# ESP32S3.net
KiCad netlist of a schematic drawn in Altium Designer
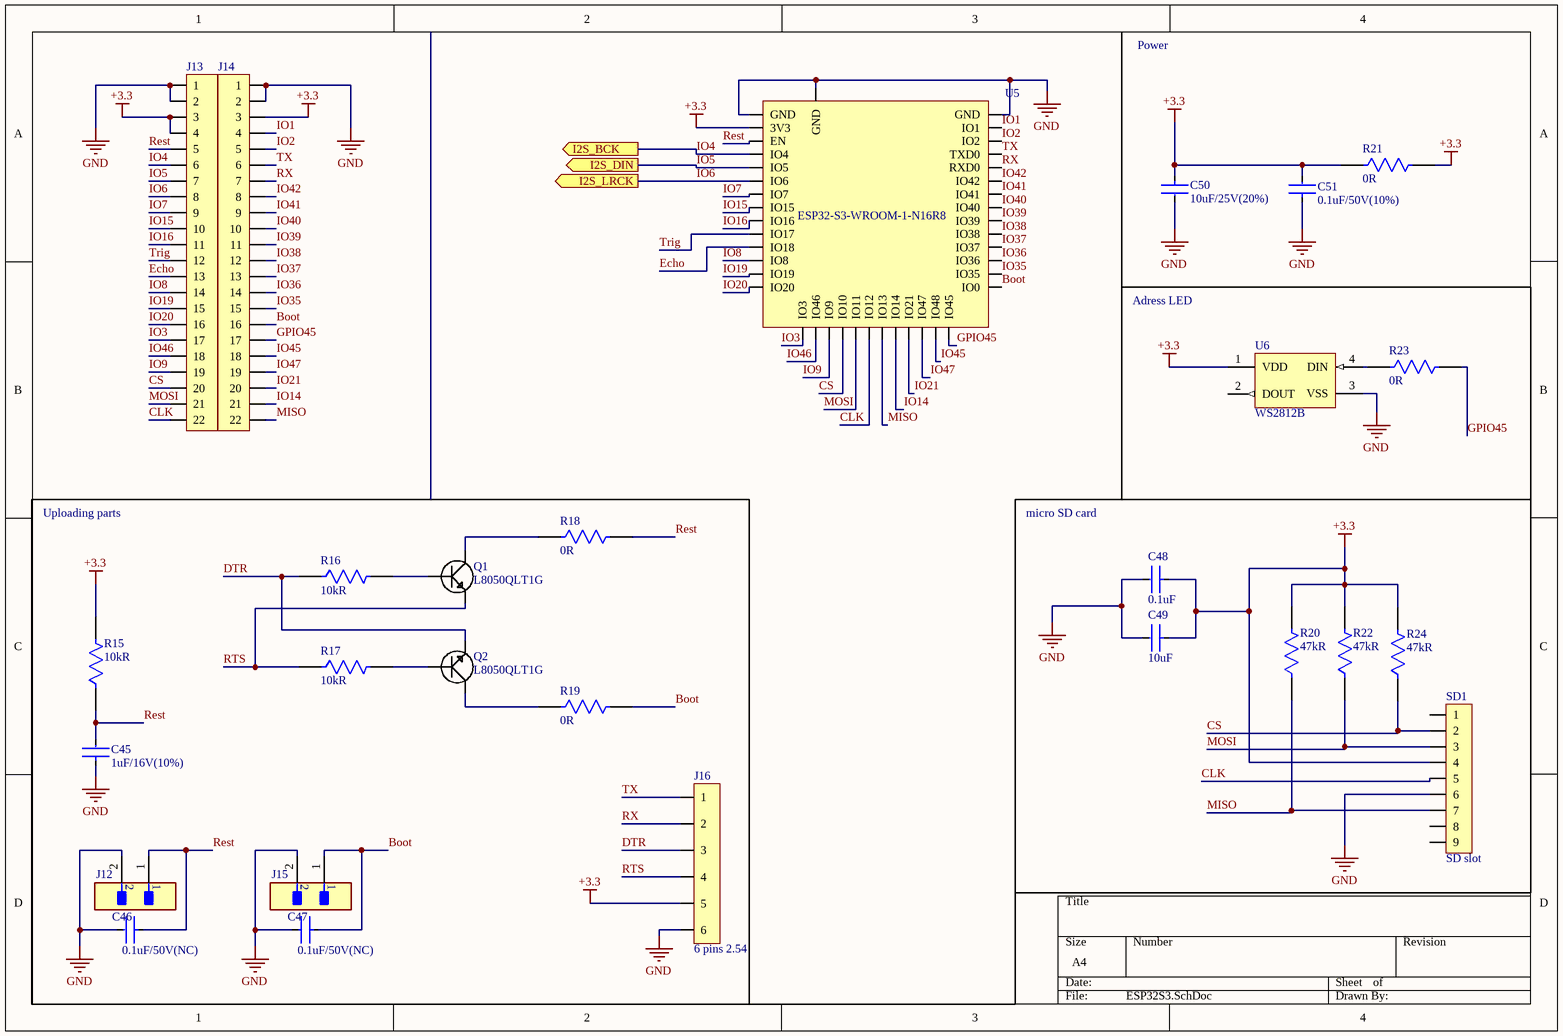
[diagram p0: ESP32S3.SchDoc]

(export (version "E")
  (design (tool "Eeschema 10.0.6"))
  (components
    (comp (ref "C45")
      (value "1uF/16V(10%)")
      (footprint "FP-CL21-IPC_C")
      (description "CL21 Series 0805 47nF 50V ±5% Tolerance X7R Multilayer Ceramic Chip Capacitor")
      (fields (field (name "TOLERANCE") "5%"))
      (libsource (lib "Altium Content Vault") (part "b4654b650e69147ec39a6b967a45e02"))
    )
    (comp (ref "C46")
      (value "0.1uF/50V(NC)")
      (footprint "FP-CL21-IPC_C")
      (description "CL21 Series 0805 47nF 50V ±5% Tolerance X7R Multilayer Ceramic Chip Capacitor")
      (fields (field (name "TOLERANCE") "5%"))
      (libsource (lib "Altium Content Vault") (part "b4654b650e69147ec39a6b967a45e02"))
    )
    (comp (ref "C47")
      (value "0.1uF/50V(NC)")
      (footprint "FP-CL21-IPC_C")
      (description "CL21 Series 0805 47nF 50V ±5% Tolerance X7R Multilayer Ceramic Chip Capacitor")
      (fields (field (name "TOLERANCE") "5%"))
      (libsource (lib "Altium Content Vault") (part "b4654b650e69147ec39a6b967a45e02"))
    )
    (comp (ref "C48")
      (value "0.1uF")
      (footprint "FP-CL21-IPC_C")
      (description "CL21 Series 0805 47nF 50V ±5% Tolerance X7R Multilayer Ceramic Chip Capacitor")
      (fields (field (name "TOLERANCE") "5%"))
      (libsource (lib "Altium Content Vault") (part "b4654b650e69147ec39a6b967a45e02"))
    )
    (comp (ref "C49")
      (value "10uF")
      (footprint "FP-CL21-IPC_C")
      (description "CL21 Series 0805 47nF 50V ±5% Tolerance X7R Multilayer Ceramic Chip Capacitor")
      (fields (field (name "TOLERANCE") "5%"))
      (libsource (lib "Altium Content Vault") (part "b4654b650e69147ec39a6b967a45e02"))
    )
    (comp (ref "C50")
      (value "10uF/25V(20%)")
      (footprint "FP-CL21-IPC_C")
      (description "CL21 Series 0805 47nF 50V ±5% Tolerance X7R Multilayer Ceramic Chip Capacitor")
      (fields (field (name "TOLERANCE") "5%"))
      (libsource (lib "Altium Content Vault") (part "b4654b650e69147ec39a6b967a45e02"))
    )
    (comp (ref "C51")
      (value "0.1uF/50V(10%)")
      (footprint "FP-CL21-IPC_C")
      (description "CL21 Series 0805 47nF 50V ±5% Tolerance X7R Multilayer Ceramic Chip Capacitor")
      (fields (field (name "TOLERANCE") "5%"))
      (libsource (lib "Altium Content Vault") (part "b4654b650e69147ec39a6b967a45e02"))
    )
    (comp (ref "J12")
      (value "M22-2510205")
      (footprint "FP-M22-2510205-MFG")
      (description "CONN HEADER VERT 2POS 2MM")
      (fields
        (field (name "MANUFACTURER") "Harwin")
        (field (name "OCTOPART") "https://octopart.com/m22-2510205-harwin-2538221")
      )
      (libsource (lib "Altium Content Vault") (part "3bc925449376181038e59eaffc5286c"))
    )
    (comp (ref "J13")
      (value "22 pins")
      (footprint "22 pins")
      (libsource (lib "Schemati_design") (part "22 pins"))
    )
    (comp (ref "J14") (value "22 pins") (footprint "22 pins") (libsource (lib "") (part "22 pins_1")))
    (comp (ref "J15")
      (value "M22-2510205")
      (footprint "FP-M22-2510205-MFG")
      (description "CONN HEADER VERT 2POS 2MM")
      (fields
        (field (name "MANUFACTURER") "Harwin")
        (field (name "OCTOPART") "https://octopart.com/m22-2510205-harwin-2538221")
      )
      (libsource (lib "Altium Content Vault") (part "3bc925449376181038e59eaffc5286c"))
    )
    (comp (ref "J16")
      (value "6 pins 2.54")
      (footprint "6 pins 2.54mm")
      (libsource (lib "Schemati_design") (part "6 pins 2.54"))
    )
    (comp (ref "Q1")
      (value "L8050QLT1G")
      (footprint "SOT95P245X110-3N")
      (libsource (lib "Schemati_design") (part "L8050QLT1G"))
    )
    (comp (ref "Q2")
      (value "L8050QLT1G")
      (footprint "SOT95P245X110-3N")
      (libsource (lib "Schemati_design") (part "L8050QLT1G"))
    )
    (comp (ref "R15")
      (value "10kR")
      (footprint "FP-RP732A-IPC_C")
      (fields (field (name "TOLERANCE") "0.1%"))
      (libsource (lib "Altium Content Vault") (part "1029c3af85768c4190bb7ad29bc67b5"))
    )
    (comp (ref "R16")
      (value "10kR")
      (footprint "FP-RP732A-IPC_C")
      (fields (field (name "TOLERANCE") "0.1%"))
      (libsource (lib "Altium Content Vault") (part "1029c3af85768c4190bb7ad29bc67b5"))
    )
    (comp (ref "R17")
      (value "10kR")
      (footprint "FP-RP732A-IPC_C")
      (fields (field (name "TOLERANCE") "0.1%"))
      (libsource (lib "Altium Content Vault") (part "1029c3af85768c4190bb7ad29bc67b5"))
    )
    (comp (ref "R18")
      (value "0R")
      (footprint "FP-RP732A-IPC_C")
      (fields (field (name "TOLERANCE") "0.1%"))
      (libsource (lib "Altium Content Vault") (part "1029c3af85768c4190bb7ad29bc67b5"))
    )
    (comp (ref "R19")
      (value "0R")
      (footprint "FP-RP732A-IPC_C")
      (fields (field (name "TOLERANCE") "0.1%"))
      (libsource (lib "Altium Content Vault") (part "1029c3af85768c4190bb7ad29bc67b5"))
    )
    (comp (ref "R20")
      (value "47kR")
      (footprint "FP-RP732A-IPC_C")
      (fields (field (name "TOLERANCE") "0.1%"))
      (libsource (lib "Altium Content Vault") (part "1029c3af85768c4190bb7ad29bc67b5"))
    )
    (comp (ref "R21")
      (value "0R")
      (footprint "FP-RP732A-IPC_C")
      (fields (field (name "TOLERANCE") "0.1%"))
      (libsource (lib "Altium Content Vault") (part "1029c3af85768c4190bb7ad29bc67b5"))
    )
    (comp (ref "R22")
      (value "47kR")
      (footprint "FP-RP732A-IPC_C")
      (fields (field (name "TOLERANCE") "0.1%"))
      (libsource (lib "Altium Content Vault") (part "1029c3af85768c4190bb7ad29bc67b5"))
    )
    (comp (ref "R23")
      (value "0R")
      (footprint "FP-RP732A-IPC_C")
      (fields (field (name "TOLERANCE") "0.1%"))
      (libsource (lib "Altium Content Vault") (part "1029c3af85768c4190bb7ad29bc67b5"))
    )
    (comp (ref "R24")
      (value "47kR")
      (footprint "FP-RP732A-IPC_C")
      (fields (field (name "TOLERANCE") "0.1%"))
      (libsource (lib "Altium Content Vault") (part "1029c3af85768c4190bb7ad29bc67b5"))
    )
    (comp (ref "SD1")
      (value "SD slot")
      (footprint "Micro SD slot")
      (libsource (lib "Schemati_design") (part "SD slot"))
    )
    (comp (ref "U5")
      (value "ESP32-S3-WROOM-1-N16R8")
      (footprint "ESP32_S3_Wroom1")
      (description "SMD mod, ESP32-S3R8 with 3.3V, 8MB Octal PSRAM die insid, 6MBQuad SPI flash, pcb ant")
      (fields (field (name "MANUFACTURER") "Espressif Systems"))
      (libsource (lib "Schemati_design") (part "ESP32-S3-WROOM-1-N16R8"))
    )
    (comp (ref "U6")
      (value "WS2812B")
      (footprint "ADA-RGB-1655_V")
      (fields (field (name "MANUFACTURER") "Adafruit-Industries-LLC"))
      (libsource (lib "Altium Content Vault") (part "ADA-RGB-1655-4"))
    )
  )
  (nets
    (net (code "1") (name "+3.3") (class "Default")
      (node (ref "C48") (pin "1") (pinfunction "1_1") (pintype "passive"))
      (node (ref "C49") (pin "1") (pinfunction "1_1") (pintype "passive"))
      (node (ref "C50") (pin "1") (pinfunction "1_1") (pintype "passive"))
      (node (ref "C51") (pin "2") (pinfunction "2_2") (pintype "passive"))
      (node (ref "J13") (pin "3") (pinfunction "3_3") (pintype "passive"))
      (node (ref "J13") (pin "4") (pinfunction "4_4") (pintype "passive"))
      (node (ref "J14") (pin "3") (pinfunction "3_3") (pintype "passive"))
      (node (ref "J16") (pin "5") (pinfunction "5_5") (pintype "passive"))
      (node (ref "R15") (pin "2") (pinfunction "2_2") (pintype "passive"))
      (node (ref "R20") (pin "2") (pinfunction "2_2") (pintype "passive"))
      (node (ref "R21") (pin "1") (pinfunction "1_1") (pintype "passive"))
      (node (ref "R21") (pin "2") (pinfunction "2_2") (pintype "passive"))
      (node (ref "R22") (pin "2") (pinfunction "2_2") (pintype "passive"))
      (node (ref "R24") (pin "2") (pinfunction "2_2") (pintype "passive"))
      (node (ref "SD1") (pin "4") (pinfunction "4_4") (pintype "passive"))
      (node (ref "U5") (pin "2") (pinfunction "3V3_2") (pintype "passive"))
      (node (ref "U6") (pin "1") (pinfunction "VDD_1") (pintype "power_in"))
    )
    (net (code "2") (name "/Boot") (class "Default")
      (node (ref "C47") (pin "1") (pinfunction "1_1") (pintype "passive"))
      (node (ref "J14") (pin "16") (pinfunction "16_16") (pintype "passive"))
      (node (ref "J15") (pin "1") (pinfunction "1_1") (pintype "passive"))
      (node (ref "R19") (pin "2") (pinfunction "2_2") (pintype "passive"))
      (node (ref "U5") (pin "27") (pinfunction "IO0_27") (pintype "passive"))
    )
    (net (code "3") (name "/CLK") (class "Default")
      (node (ref "J13") (pin "22") (pinfunction "22_22") (pintype "passive"))
      (node (ref "SD1") (pin "5") (pinfunction "5_5") (pintype "passive"))
      (node (ref "U5") (pin "20") (pinfunction "IO12_20") (pintype "passive"))
    )
    (net (code "4") (name "/CS") (class "Default")
      (node (ref "J13") (pin "20") (pinfunction "20_20") (pintype "passive"))
      (node (ref "R24") (pin "1") (pinfunction "1_1") (pintype "passive"))
      (node (ref "SD1") (pin "2") (pinfunction "2_2") (pintype "passive"))
      (node (ref "U5") (pin "18") (pinfunction "IO10_18") (pintype "passive"))
    )
    (net (code "5") (name "/DTR") (class "Default")
      (node (ref "J16") (pin "3") (pinfunction "3_3") (pintype "passive"))
      (node (ref "Q2") (pin "2") (pinfunction "Emitter_2") (pintype "passive"))
      (node (ref "R16") (pin "1") (pinfunction "1_1") (pintype "passive"))
    )
    (net (code "6") (name "/Echo") (class "Default")
      (node (ref "J13") (pin "13") (pinfunction "13_13") (pintype "passive"))
      (node (ref "U5") (pin "11") (pinfunction "IO18_11") (pintype "passive"))
    )
    (net (code "7") (name "/GPIO45") (class "Default")
      (node (ref "J14") (pin "17") (pinfunction "17_17") (pintype "passive"))
      (node (ref "R23") (pin "2") (pinfunction "2_2") (pintype "passive"))
      (node (ref "U5") (pin "26") (pinfunction "IO45_26") (pintype "passive"))
    )
    (net (code "8") (name "/IO1") (class "Default")
      (node (ref "J14") (pin "4") (pinfunction "4_4") (pintype "passive"))
      (node (ref "U5") (pin "39") (pinfunction "IO1_39") (pintype "passive"))
    )
    (net (code "9") (name "/IO2") (class "Default")
      (node (ref "J14") (pin "5") (pinfunction "5_5") (pintype "passive"))
      (node (ref "U5") (pin "38") (pinfunction "IO2_38") (pintype "passive"))
    )
    (net (code "10") (name "/IO3") (class "Default")
      (node (ref "J13") (pin "17") (pinfunction "17_17") (pintype "passive"))
      (node (ref "U5") (pin "15") (pinfunction "IO3_15") (pintype "passive"))
    )
    (net (code "11") (name "/IO4") (class "Default")
      (node (ref "J13") (pin "6") (pinfunction "6_6") (pintype "passive"))
      (node (ref "U5") (pin "4") (pinfunction "IO4_4") (pintype "passive"))
    )
    (net (code "12") (name "/IO5") (class "Default")
      (node (ref "J13") (pin "7") (pinfunction "7_7") (pintype "passive"))
      (node (ref "U5") (pin "5") (pinfunction "IO5_5") (pintype "passive"))
    )
    (net (code "13") (name "/IO6") (class "Default")
      (node (ref "J13") (pin "8") (pinfunction "8_8") (pintype "passive"))
      (node (ref "U5") (pin "6") (pinfunction "IO6_6") (pintype "passive"))
    )
    (net (code "14") (name "/IO7") (class "Default")
      (node (ref "J13") (pin "9") (pinfunction "9_9") (pintype "passive"))
      (node (ref "U5") (pin "7") (pinfunction "IO7_7") (pintype "passive"))
    )
    (net (code "15") (name "/IO8") (class "Default")
      (node (ref "J13") (pin "14") (pinfunction "14_14") (pintype "passive"))
      (node (ref "U5") (pin "12") (pinfunction "IO8_12") (pintype "passive"))
    )
    (net (code "16") (name "/IO9") (class "Default")
      (node (ref "J13") (pin "19") (pinfunction "19_19") (pintype "passive"))
      (node (ref "U5") (pin "17") (pinfunction "IO9_17") (pintype "passive"))
    )
    (net (code "17") (name "/IO14") (class "Default")
      (node (ref "J14") (pin "21") (pinfunction "21_21") (pintype "passive"))
      (node (ref "U5") (pin "22") (pinfunction "IO14_22") (pintype "passive"))
    )
    (net (code "18") (name "/IO15") (class "Default")
      (node (ref "J13") (pin "10") (pinfunction "10_10") (pintype "passive"))
      (node (ref "U5") (pin "8") (pinfunction "IO15_8") (pintype "passive"))
    )
    (net (code "19") (name "/IO16") (class "Default")
      (node (ref "J13") (pin "11") (pinfunction "11_11") (pintype "passive"))
      (node (ref "U5") (pin "9") (pinfunction "IO16_9") (pintype "passive"))
    )
    (net (code "20") (name "/IO19") (class "Default")
      (node (ref "J13") (pin "15") (pinfunction "15_15") (pintype "passive"))
      (node (ref "U5") (pin "13") (pinfunction "IO19_13") (pintype "passive"))
    )
    (net (code "21") (name "/IO20") (class "Default")
      (node (ref "J13") (pin "16") (pinfunction "16_16") (pintype "passive"))
      (node (ref "U5") (pin "14") (pinfunction "IO20_14") (pintype "passive"))
    )
    (net (code "22") (name "/IO21") (class "Default")
      (node (ref "J14") (pin "20") (pinfunction "20_20") (pintype "passive"))
      (node (ref "U5") (pin "23") (pinfunction "IO21_23") (pintype "passive"))
    )
    (net (code "23") (name "/IO35") (class "Default")
      (node (ref "J14") (pin "15") (pinfunction "15_15") (pintype "passive"))
      (node (ref "U5") (pin "28") (pinfunction "IO35_28") (pintype "passive"))
    )
    (net (code "24") (name "/IO36") (class "Default")
      (node (ref "J14") (pin "14") (pinfunction "14_14") (pintype "passive"))
      (node (ref "U5") (pin "29") (pinfunction "IO36_29") (pintype "passive"))
    )
    (net (code "25") (name "/IO37") (class "Default")
      (node (ref "J14") (pin "13") (pinfunction "13_13") (pintype "passive"))
      (node (ref "U5") (pin "30") (pinfunction "IO37_30") (pintype "passive"))
    )
    (net (code "26") (name "/IO38") (class "Default")
      (node (ref "J14") (pin "12") (pinfunction "12_12") (pintype "passive"))
      (node (ref "U5") (pin "31") (pinfunction "IO38_31") (pintype "passive"))
    )
    (net (code "27") (name "/IO39") (class "Default")
      (node (ref "J14") (pin "11") (pinfunction "11_11") (pintype "passive"))
      (node (ref "U5") (pin "32") (pinfunction "IO39_32") (pintype "passive"))
    )
    (net (code "28") (name "/IO40") (class "Default")
      (node (ref "J14") (pin "10") (pinfunction "10_10") (pintype "passive"))
      (node (ref "U5") (pin "33") (pinfunction "IO40_33") (pintype "passive"))
    )
    (net (code "29") (name "/IO41") (class "Default")
      (node (ref "J14") (pin "9") (pinfunction "9_9") (pintype "passive"))
      (node (ref "U5") (pin "34") (pinfunction "IO41_34") (pintype "passive"))
    )
    (net (code "30") (name "/IO42") (class "Default")
      (node (ref "J14") (pin "8") (pinfunction "8_8") (pintype "passive"))
      (node (ref "U5") (pin "35") (pinfunction "IO42_35") (pintype "passive"))
    )
    (net (code "31") (name "/IO45") (class "Default")
      (node (ref "J14") (pin "18") (pinfunction "18_18") (pintype "passive"))
      (node (ref "U5") (pin "25") (pinfunction "IO48_25") (pintype "passive"))
    )
    (net (code "32") (name "/IO46") (class "Default")
      (node (ref "J13") (pin "18") (pinfunction "18_18") (pintype "passive"))
      (node (ref "U5") (pin "16") (pinfunction "IO46_16") (pintype "passive"))
    )
    (net (code "33") (name "/IO47") (class "Default")
      (node (ref "J14") (pin "19") (pinfunction "19_19") (pintype "passive"))
      (node (ref "U5") (pin "24") (pinfunction "IO47_24") (pintype "passive"))
    )
    (net (code "34") (name "/MISO") (class "Default")
      (node (ref "J14") (pin "22") (pinfunction "22_22") (pintype "passive"))
      (node (ref "R20") (pin "1") (pinfunction "1_1") (pintype "passive"))
      (node (ref "SD1") (pin "7") (pinfunction "7_7") (pintype "passive"))
      (node (ref "U5") (pin "21") (pinfunction "IO13_21") (pintype "passive"))
    )
    (net (code "35") (name "/MOSI") (class "Default")
      (node (ref "J13") (pin "21") (pinfunction "21_21") (pintype "passive"))
      (node (ref "R22") (pin "1") (pinfunction "1_1") (pintype "passive"))
      (node (ref "SD1") (pin "3") (pinfunction "3_3") (pintype "passive"))
      (node (ref "U5") (pin "19") (pinfunction "IO11_19") (pintype "passive"))
    )
    (net (code "36") (name "/RTS") (class "Default")
      (node (ref "J16") (pin "4") (pinfunction "4_4") (pintype "passive"))
      (node (ref "Q1") (pin "2") (pinfunction "Emitter_2") (pintype "passive"))
      (node (ref "R17") (pin "1") (pinfunction "1_1") (pintype "passive"))
    )
    (net (code "37") (name "/RX") (class "Default")
      (node (ref "J14") (pin "7") (pinfunction "7_7") (pintype "passive"))
      (node (ref "J16") (pin "2") (pinfunction "2_2") (pintype "passive"))
      (node (ref "U5") (pin "36") (pinfunction "RXD0_36") (pintype "passive"))
    )
    (net (code "38") (name "/Rest") (class "Default")
      (node (ref "C45") (pin "2") (pinfunction "2_2") (pintype "passive"))
      (node (ref "C46") (pin "1") (pinfunction "1_1") (pintype "passive"))
      (node (ref "J12") (pin "1") (pinfunction "1_1") (pintype "passive"))
      (node (ref "J13") (pin "5") (pinfunction "5_5") (pintype "passive"))
      (node (ref "R15") (pin "1") (pinfunction "1_1") (pintype "passive"))
      (node (ref "R18") (pin "2") (pinfunction "2_2") (pintype "passive"))
      (node (ref "U5") (pin "3") (pinfunction "EN_3") (pintype "passive"))
    )
    (net (code "39") (name "/TX") (class "Default")
      (node (ref "J14") (pin "6") (pinfunction "6_6") (pintype "passive"))
      (node (ref "J16") (pin "1") (pinfunction "1_1") (pintype "passive"))
      (node (ref "U5") (pin "37") (pinfunction "TXD0_37") (pintype "passive"))
    )
    (net (code "40") (name "/Trig") (class "Default")
      (node (ref "J13") (pin "12") (pinfunction "12_12") (pintype "passive"))
      (node (ref "U5") (pin "10") (pinfunction "IO17_10") (pintype "passive"))
    )
    (net (code "41") (name "GND") (class "Default")
      (node (ref "C45") (pin "1") (pinfunction "1_1") (pintype "passive"))
      (node (ref "C46") (pin "2") (pinfunction "2_2") (pintype "passive"))
      (node (ref "C47") (pin "2") (pinfunction "2_2") (pintype "passive"))
      (node (ref "C48") (pin "2") (pinfunction "2_2") (pintype "passive"))
      (node (ref "C49") (pin "2") (pinfunction "2_2") (pintype "passive"))
      (node (ref "C50") (pin "2") (pinfunction "2_2") (pintype "passive"))
      (node (ref "C51") (pin "1") (pinfunction "1_1") (pintype "passive"))
      (node (ref "J12") (pin "2") (pinfunction "2_2") (pintype "passive"))
      (node (ref "J13") (pin "1") (pinfunction "1_1") (pintype "passive"))
      (node (ref "J13") (pin "2") (pinfunction "2_2") (pintype "passive"))
      (node (ref "J14") (pin "1") (pinfunction "1_1") (pintype "passive"))
      (node (ref "J14") (pin "2") (pinfunction "2_2") (pintype "passive"))
      (node (ref "J15") (pin "2") (pinfunction "2_2") (pintype "passive"))
      (node (ref "J16") (pin "6") (pinfunction "6_6") (pintype "passive"))
      (node (ref "SD1") (pin "6") (pinfunction "6_6") (pintype "passive"))
      (node (ref "U5") (pin "1") (pinfunction "GND_1") (pintype "passive"))
      (node (ref "U5") (pin "40") (pinfunction "GND_40") (pintype "passive"))
      (node (ref "U5") (pin "41") (pinfunction "GND_41") (pintype "passive"))
      (node (ref "U6") (pin "3") (pinfunction "VSS_3") (pintype "power_in"))
    )
    (net (code "42") (name "Net-(Q1-Base)") (class "Default")
      (node (ref "Q1") (pin "1") (pinfunction "Base_1") (pintype "passive"))
      (node (ref "R16") (pin "2") (pinfunction "2_2") (pintype "passive"))
    )
    (net (code "43") (name "Net-(Q1-Collector)") (class "Default")
      (node (ref "Q1") (pin "3") (pinfunction "Collector_3") (pintype "passive"))
      (node (ref "R18") (pin "1") (pinfunction "1_1") (pintype "passive"))
    )
    (net (code "44") (name "Net-(Q2-Base)") (class "Default")
      (node (ref "Q2") (pin "1") (pinfunction "Base_1") (pintype "passive"))
      (node (ref "R17") (pin "2") (pinfunction "2_2") (pintype "passive"))
    )
    (net (code "45") (name "Net-(Q2-Collector)") (class "Default")
      (node (ref "Q2") (pin "3") (pinfunction "Collector_3") (pintype "passive"))
      (node (ref "R19") (pin "1") (pinfunction "1_1") (pintype "passive"))
    )
    (net (code "46") (name "Net-(U6-DIN)") (class "Default")
      (node (ref "R23") (pin "1") (pinfunction "1_1") (pintype "passive"))
      (node (ref "U6") (pin "4") (pinfunction "DIN_4") (pintype "input"))
    )
    (net (code "47") (name "unconnected-(SD1-Pad1)") (class "Default")
      (node (ref "SD1") (pin "1") (pinfunction "1_1") (pintype "passive"))
    )
    (net (code "48") (name "unconnected-(SD1-Pad8)") (class "Default")
      (node (ref "SD1") (pin "8") (pinfunction "8_8") (pintype "passive"))
    )
    (net (code "49") (name "unconnected-(SD1-Pad9)") (class "Default")
      (node (ref "SD1") (pin "9") (pinfunction "9_9") (pintype "passive"))
    )
    (net (code "50") (name "unconnected-(U6-DOUT-Pad2)") (class "Default")
      (node (ref "U6") (pin "2") (pinfunction "DOUT_2") (pintype "output"))
    )
  )
)
